# Others.net
KiCad netlist of a schematic drawn in Altium Designer
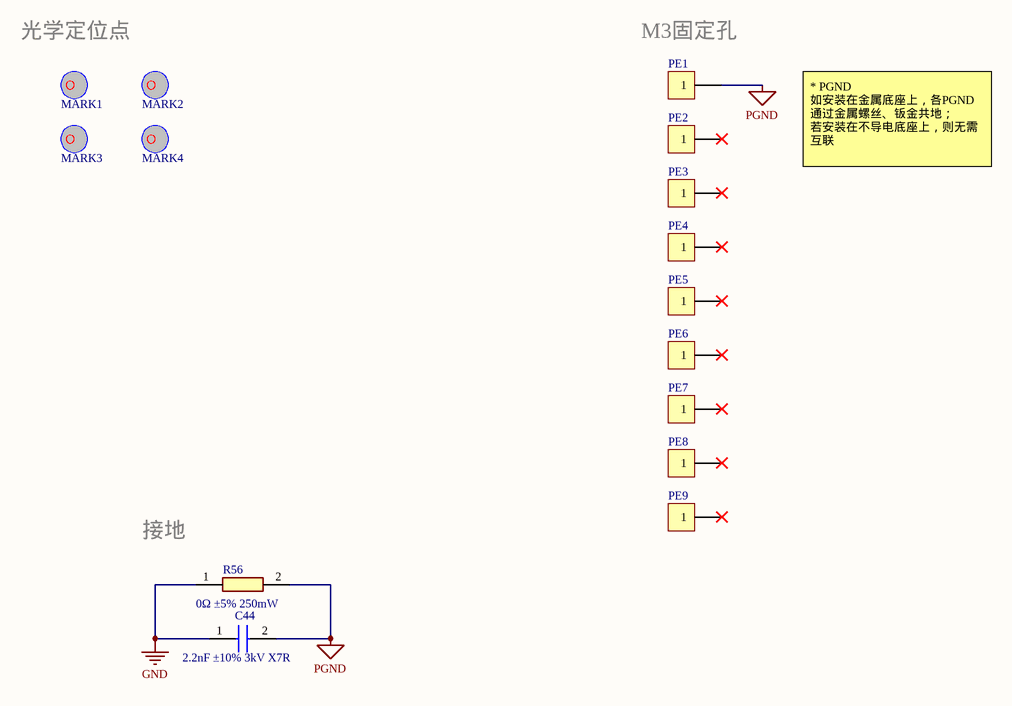
[diagram p0: Others.SchDoc]

(export (version "E")
  (design (tool "Eeschema 10.0.6"))
  (components
    (comp (ref "C44")
      (value "2.2nF ±10% 3kV X7R")
      (footprint "SamacSys:CAPC4532X320N")
      (description "HV1812Y222KXHATHV\r\n2.2nF\r\n精度: ±10%\r\n额定电压: 3kV\r\n材质(温度系数): X7R\r\n1812")
      (fields
        (field (name "MANUFACTURER_PART_NUMBER") "HV1812Y222KXHATHV")
        (field (name "MOUSER PART NUMBER") "77-HV1812Y222KXHATHV")
      )
      (libsource (lib "*") (part "HV1812Y222KXHATHV"))
    )
    (comp (ref "MARK1")
      (value "MARK_POINT")
      (footprint "MARK_POINT")
      (libsource (lib "others") (part "MARK_POINT"))
    )
    (comp (ref "MARK2")
      (value "MARK_POINT")
      (footprint "MARK_POINT")
      (libsource (lib "others") (part "MARK_POINT"))
    )
    (comp (ref "MARK3")
      (value "MARK_POINT")
      (footprint "MARK_POINT")
      (libsource (lib "others") (part "MARK_POINT"))
    )
    (comp (ref "MARK4")
      (value "MARK_POINT")
      (footprint "MARK_POINT")
      (libsource (lib "others") (part "MARK_POINT"))
    )
    (comp (ref "PE1")
      (value "~")
      (footprint "固定孔-M3")
      (description "Connector")
      (libsource (lib "*") (part "CON1"))
    )
    (comp (ref "PE2")
      (value "~")
      (footprint "固定孔-M3")
      (description "Connector")
      (libsource (lib "*") (part "CON1"))
    )
    (comp (ref "PE3")
      (value "~")
      (footprint "固定孔-M3")
      (description "Connector")
      (libsource (lib "*") (part "CON1"))
    )
    (comp (ref "PE4")
      (value "~")
      (footprint "固定孔-M3")
      (description "Connector")
      (libsource (lib "*") (part "CON1"))
    )
    (comp (ref "PE5")
      (value "~")
      (footprint "固定孔-M3")
      (description "Connector")
      (libsource (lib "*") (part "CON1"))
    )
    (comp (ref "PE6")
      (value "~")
      (footprint "固定孔-M3")
      (description "Connector")
      (libsource (lib "*") (part "CON1"))
    )
    (comp (ref "PE7")
      (value "~")
      (footprint "固定孔-M3")
      (description "Connector")
      (libsource (lib "*") (part "CON1"))
    )
    (comp (ref "PE8")
      (value "~")
      (footprint "固定孔-M3")
      (description "Connector")
      (libsource (lib "*") (part "CON1"))
    )
    (comp (ref "PE9")
      (value "~")
      (footprint "固定孔-M3")
      (description "Connector")
      (libsource (lib "*") (part "CON1"))
    )
    (comp (ref "R56")
      (value "0Ω ±5% 250mW")
      (footprint "SamacSys:RESC3116X65N")
      (description "RC1206JR-070RL")
      (fields (field (name "MOUSER PART NUMBER") "603-RC1206JR-070RL"))
      (libsource (lib "*") (part "RC1206JR-070RL"))
    )
  )
  (nets
    (net (code "1") (name "GND") (class "Default")
      (node (ref "C44") (pin "1") (pinfunction "1_1") (pintype "passive"))
      (node (ref "R56") (pin "1") (pinfunction "1_1") (pintype "passive"))
    )
    (net (code "2") (name "PGND") (class "Default")
      (node (ref "C44") (pin "2") (pinfunction "2_2") (pintype "passive"))
      (node (ref "PE1") (pin "1") (pinfunction "1_1") (pintype "passive"))
      (node (ref "R56") (pin "2") (pinfunction "2_2") (pintype "passive"))
    )
    (net (code "3") (name "unconnected-(PE2-Pad1)") (class "Default")
      (node (ref "PE2") (pin "1") (pinfunction "1_1") (pintype "passive+no_connect"))
    )
    (net (code "4") (name "unconnected-(PE3-Pad1)") (class "Default")
      (node (ref "PE3") (pin "1") (pinfunction "1_1") (pintype "passive+no_connect"))
    )
    (net (code "5") (name "unconnected-(PE4-Pad1)") (class "Default")
      (node (ref "PE4") (pin "1") (pinfunction "1_1") (pintype "passive+no_connect"))
    )
    (net (code "6") (name "unconnected-(PE5-Pad1)") (class "Default")
      (node (ref "PE5") (pin "1") (pinfunction "1_1") (pintype "passive+no_connect"))
    )
    (net (code "7") (name "unconnected-(PE6-Pad1)") (class "Default")
      (node (ref "PE6") (pin "1") (pinfunction "1_1") (pintype "passive+no_connect"))
    )
    (net (code "8") (name "unconnected-(PE7-Pad1)") (class "Default")
      (node (ref "PE7") (pin "1") (pinfunction "1_1") (pintype "passive+no_connect"))
    )
    (net (code "9") (name "unconnected-(PE8-Pad1)") (class "Default")
      (node (ref "PE8") (pin "1") (pinfunction "1_1") (pintype "passive+no_connect"))
    )
    (net (code "10") (name "unconnected-(PE9-Pad1)") (class "Default")
      (node (ref "PE9") (pin "1") (pinfunction "1_1") (pintype "passive+no_connect"))
    )
  )
)
